# Magnetometer_and_Electromagnet_Driver.net
KiCad netlist of a schematic drawn in Altium Designer
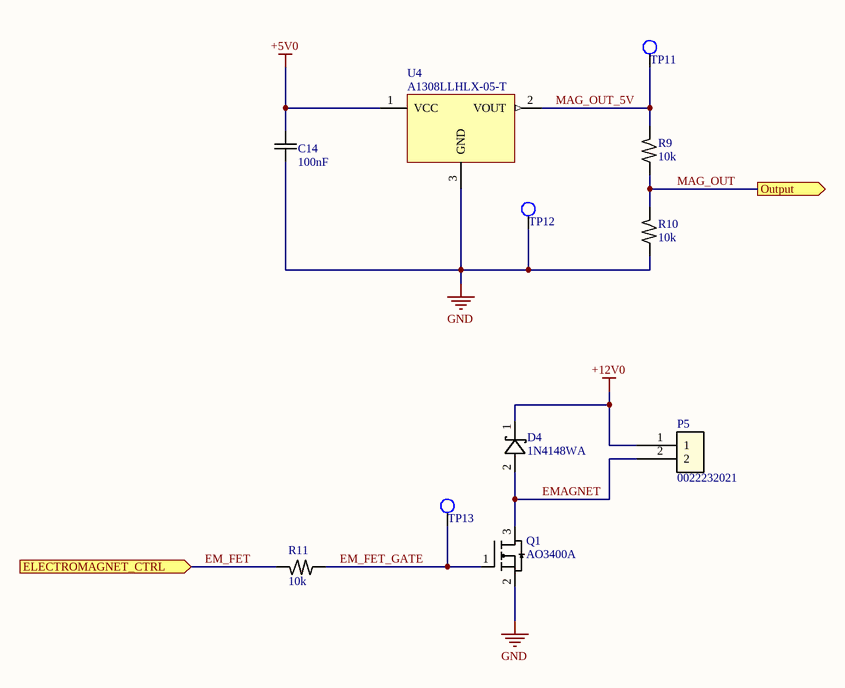
[diagram p0: Magnetometer and Electromagnet Driver.SchDoc]

(export (version "E")
  (design (tool "Eeschema 10.0.6"))
  (components
    (comp (ref "C14")
      (value "100nF")
      (footprint "C0603")
      (description "CAP CER 100nF 50V X7R 0603")
      (fields (field (name "MF") "HRE") (field (name "MP") "CGA0603X7R104K500JT"))
      (libsource (lib "Components") (part "Cap_cer"))
    )
    (comp (ref "D4")
      (value "1N4148WA")
      (footprint "SOD-123W")
      (description "DIODE GP 75V 150mA SOD-123W")
      (fields (field (name "MF") "PJSEMI"))
      (libsource (lib "Components") (part "PMEG4020ETR-QX"))
    )
    (comp (ref "P5")
      (value "0022232021")
      (footprint "Signal2")
      (description "SignalConnector, 2 leads")
      (fields (field (name "MF") "Molex"))
      (libsource (lib "Connectors") (part "Signal2"))
    )
    (comp (ref "Q1")
      (value "AO3400A")
      (footprint "SOT23-3")
      (description "MOSFET N-CH 30V SOT-23-3L")
      (fields (field (name "MF") "AOS"))
      (libsource (lib "Components") (part "AO3400A"))
    )
    (comp (ref "R9")
      (value "10k")
      (footprint "R0603")
      (description "RES 10kΩ ±1% 100mW 0603")
      (fields (field (name "MF") "FOJAN") (field (name "MP") "FRC0603F1002TS"))
      (libsource (lib "Components") (part "Res"))
    )
    (comp (ref "R10")
      (value "10k")
      (footprint "R0603")
      (description "RES 10kΩ ±1% 100mW 0603")
      (fields (field (name "MF") "FOJAN") (field (name "MP") "FRC0603F1002TS"))
      (libsource (lib "Components") (part "Res"))
    )
    (comp (ref "R11")
      (value "10k")
      (footprint "R0603")
      (description "RES 10kΩ ±1% 100mW 0603")
      (fields (field (name "MF") "FOJAN") (field (name "MP") "FRC0603F1002TS"))
      (libsource (lib "Components") (part "Res"))
    )
    (comp (ref "TP11")
      (value "TestPoint")
      (footprint "TESTPOINT_SMD_1.27MM")
      (libsource (lib "Components") (part "TestPoint"))
    )
    (comp (ref "TP12")
      (value "TestPoint")
      (footprint "TESTPOINT_SMD_1.27MM")
      (libsource (lib "Components") (part "TestPoint"))
    )
    (comp (ref "TP13")
      (value "TestPoint")
      (footprint "TESTPOINT_SMD_1.27MM")
      (libsource (lib "Components") (part "TestPoint"))
    )
    (comp (ref "U4")
      (value "A1308LLHLX-05-T")
      (footprint "SOT23-3")
      (description "SOT-23W Linear 0.5mV/Gauss, Compass (ICs) RoHS")
      (fields (field (name "MF") "ALLEGRO"))
      (libsource (lib "Components") (part "A1308LLHLX-05-T Magnetometer"))
    )
  )
  (nets
    (net (code "1") (name "+5V0") (class "Default")
      (node (ref "C14") (pin "2") (pinfunction "2_2") (pintype "passive"))
      (node (ref "U4") (pin "1") (pinfunction "VCC_1") (pintype "power_in"))
    )
    (net (code "2") (name "+12V0") (class "Default")
      (node (ref "D4") (pin "1") (pinfunction "1_1") (pintype "passive"))
      (node (ref "P5") (pin "1") (pinfunction "1_1") (pintype "passive"))
    )
    (net (code "3") (name "/EMAGNET") (class "Default")
      (node (ref "D4") (pin "2") (pinfunction "2_2") (pintype "passive"))
      (node (ref "P5") (pin "2") (pinfunction "2_2") (pintype "passive"))
      (node (ref "Q1") (pin "3") (pinfunction "G_3") (pintype "passive"))
    )
    (net (code "4") (name "/EM_FET") (class "Default")
      (node (ref "R11") (pin "2") (pinfunction "2_2") (pintype "passive"))
    )
    (net (code "5") (name "/EM_FET_GATE") (class "Default")
      (node (ref "Q1") (pin "1") (pinfunction "G_1") (pintype "passive"))
      (node (ref "R11") (pin "1") (pinfunction "1_1") (pintype "passive"))
      (node (ref "TP13") (pin "1") (pinfunction "1_1") (pintype "passive"))
    )
    (net (code "6") (name "/MAG_OUT") (class "Default")
      (node (ref "R10") (pin "2") (pinfunction "2_2") (pintype "passive"))
      (node (ref "R9") (pin "1") (pinfunction "1_1") (pintype "passive"))
    )
    (net (code "7") (name "/MAG_OUT_5V") (class "Default")
      (node (ref "R9") (pin "2") (pinfunction "2_2") (pintype "passive"))
      (node (ref "TP11") (pin "1") (pinfunction "1_1") (pintype "passive"))
      (node (ref "U4") (pin "2") (pinfunction "VOUT_2") (pintype "output"))
    )
    (net (code "8") (name "GND") (class "Default")
      (node (ref "C14") (pin "1") (pinfunction "1_1") (pintype "passive"))
      (node (ref "Q1") (pin "2") (pinfunction "G_2") (pintype "passive"))
      (node (ref "R10") (pin "1") (pinfunction "1_1") (pintype "passive"))
      (node (ref "TP12") (pin "1") (pinfunction "1_1") (pintype "passive"))
      (node (ref "U4") (pin "3") (pinfunction "GND_3") (pintype "power_in"))
    )
  )
)
